# plp-cd_4-20.net
KiCad netlist of a schematic drawn in Altium Designer
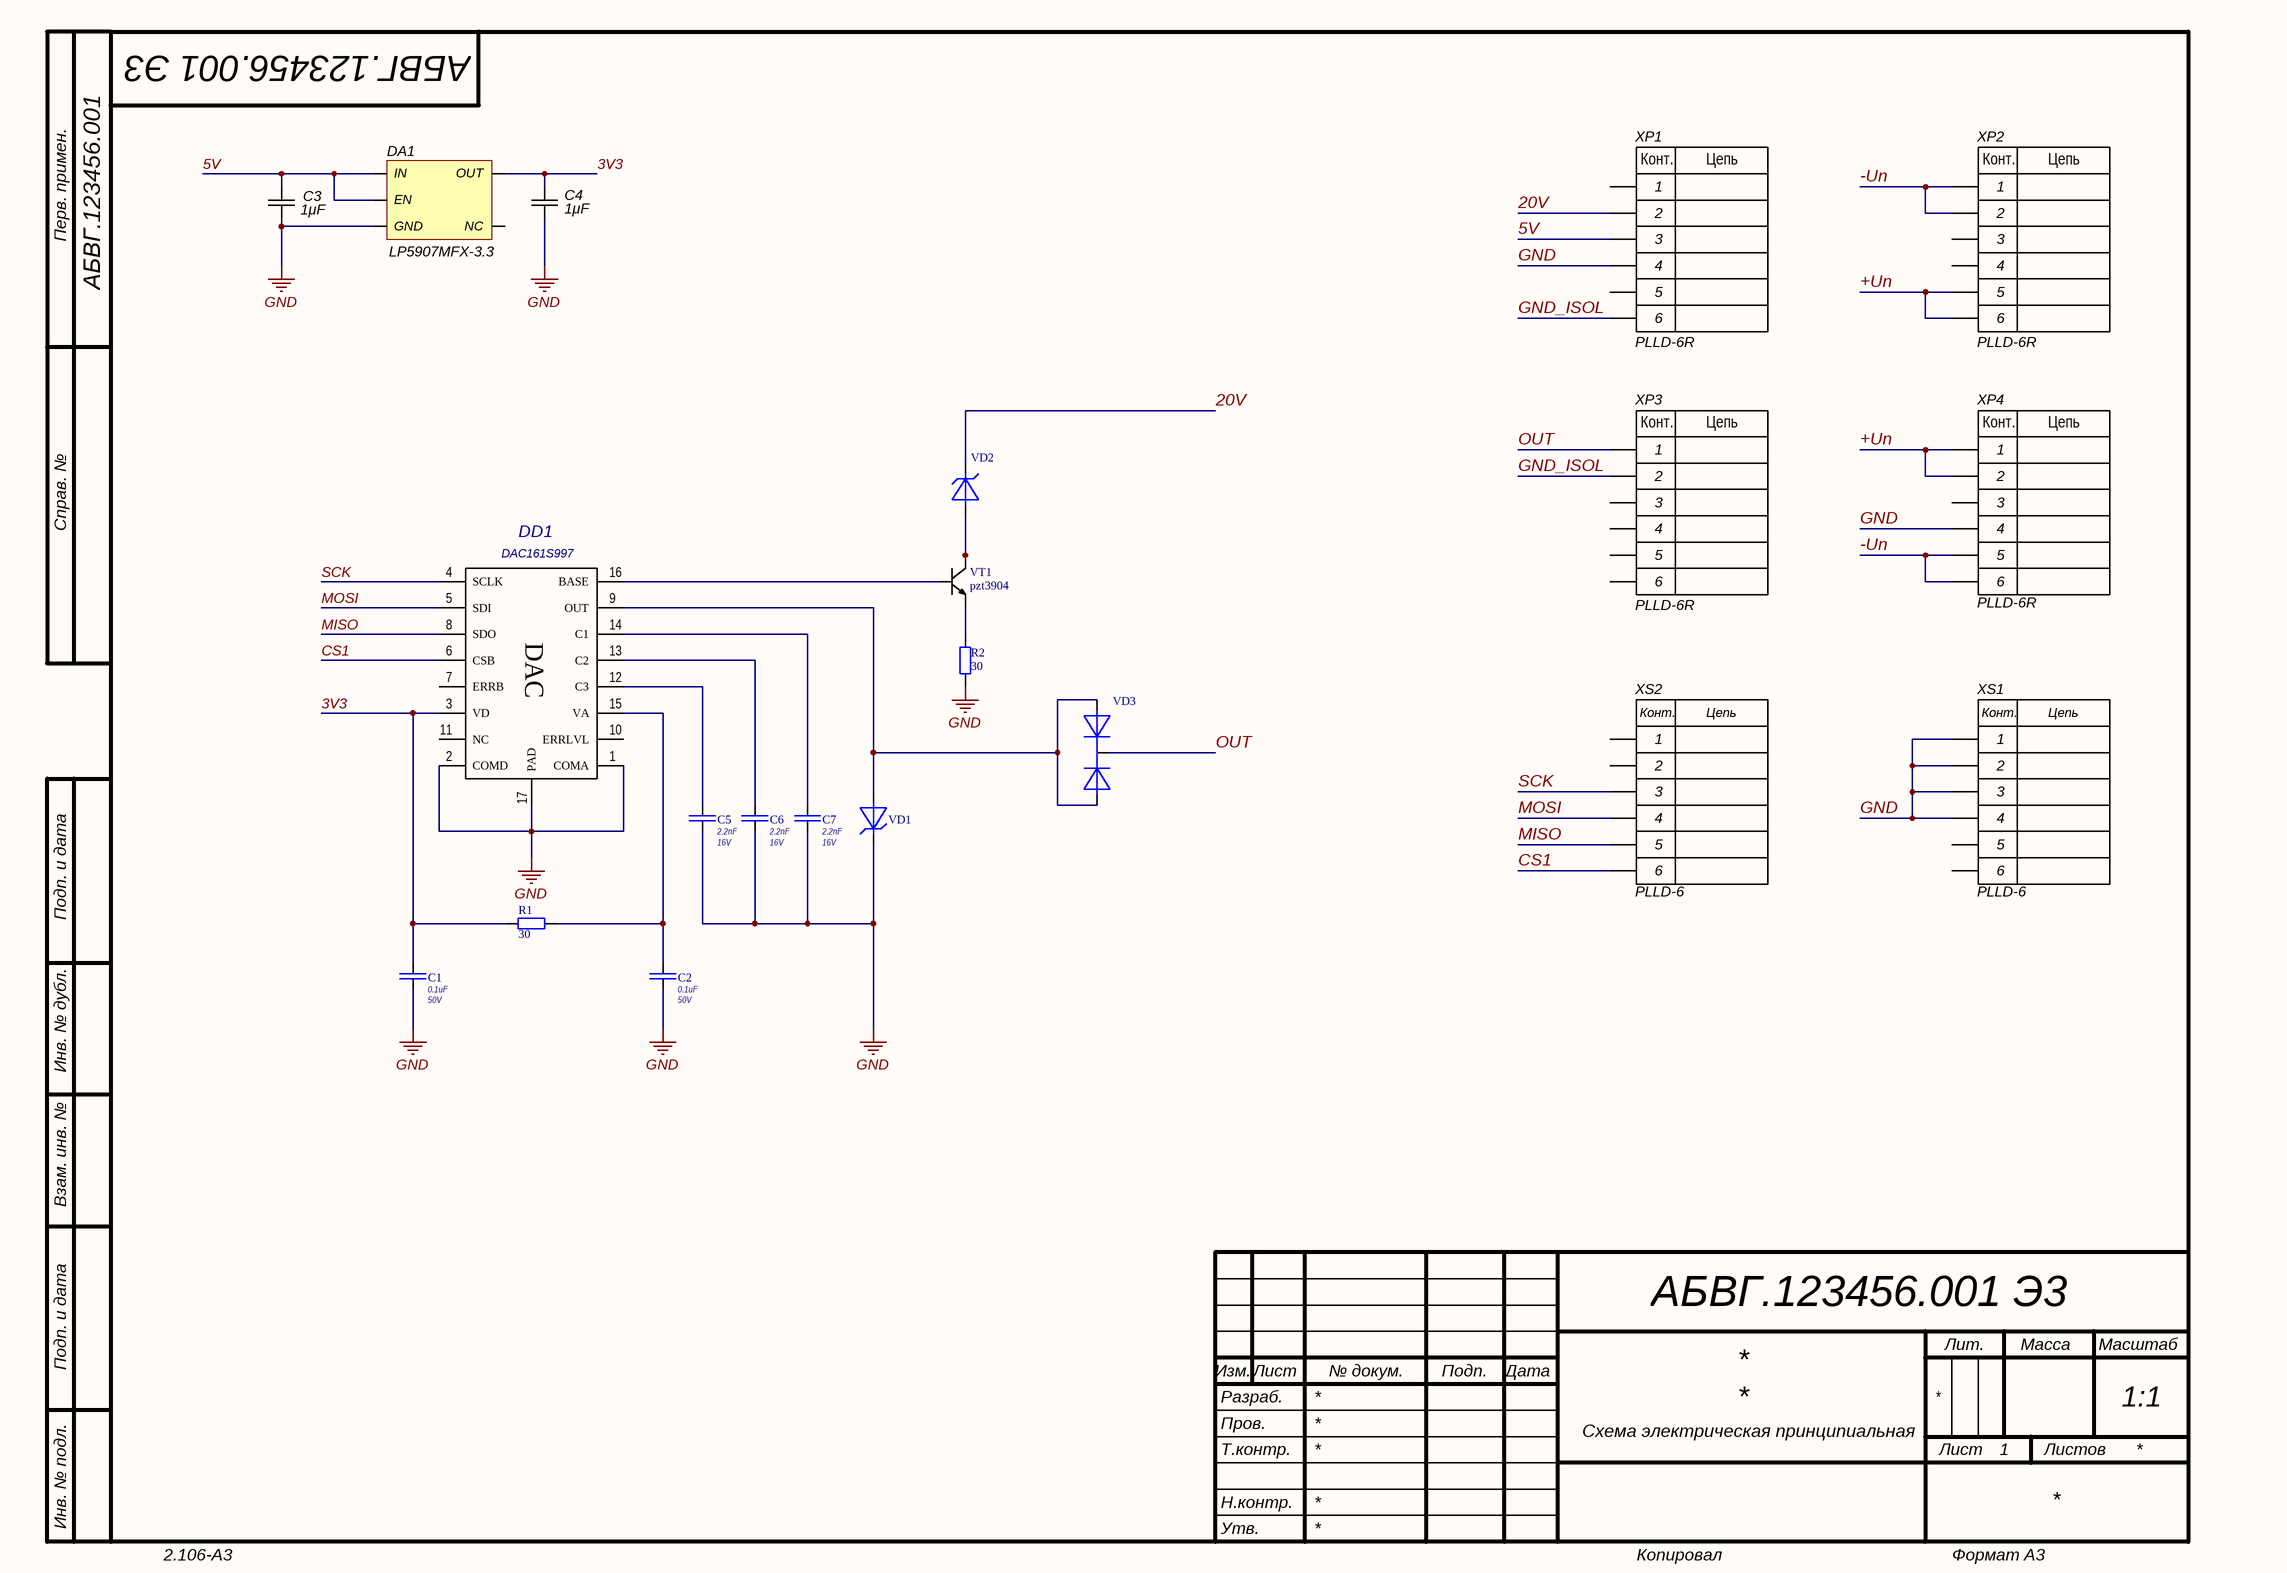
[diagram p0: plp-cd(4-20).SchDoc]

(export (version "E")
  (design (tool "Eeschema 10.0.6"))
  (components
    (comp (ref "C1")
      (value "0.1uF")
      (footprint "CAPC_0603(1608)X080L")
      (description "Конденсатор")
      (fields
        (field (name "MANUFACTURER") "Murata")
        (field (name "PARTNUMBER") "0603 - 0,1 мкФ ± 10 % - 50 В - X7R")
        (field (name "RATED DC VOLTAGE") "50V")
      )
      (libsource (lib "Chip Capacitor") (part "Capacitor Ceramic"))
    )
    (comp (ref "C2")
      (value "0.1uF")
      (footprint "CAPC_0603(1608)X080L")
      (description "Конденсатор")
      (fields
        (field (name "MANUFACTURER") "Murata")
        (field (name "PARTNUMBER") "0603 - 0,1 мкФ ± 10 % - 50 В - X7R")
        (field (name "RATED DC VOLTAGE") "50V")
      )
      (libsource (lib "Chip Capacitor") (part "Capacitor Ceramic"))
    )
    (comp (ref "C3")
      (value "1μF")
      (footprint "CAP: 0603")
      (fields
        (field (name "MANUFACTURER") "Yageo")
        (field (name "PARTNUMBER") "CC0603KRX7R7BB104")
        (field (name "VALUEMANUFACTURERPARTNUMBER") "Ceramic capacitor, 1μF, X7R, ±10%, 16V, 0603, -55...+125°C")
      )
      (libsource (lib "capacitor") (part "Ceramic_0603"))
    )
    (comp (ref "C4")
      (value "1μF")
      (footprint "CAP: 0603")
      (fields
        (field (name "MANUFACTURER") "Yageo")
        (field (name "PARTNUMBER") "CC0603KRX7R7BB104")
        (field (name "VALUEMANUFACTURERPARTNUMBER") "Ceramic capacitor, 1μF, X7R, ±10%, 16V, 0603, -55...+125°C")
      )
      (libsource (lib "capacitor") (part "Ceramic_0603"))
    )
    (comp (ref "C5")
      (value "2.2nF")
      (footprint "CAPC_0603(1608)X080L")
      (description "Конденсатор")
      (fields
        (field (name "MANUFACTURER") "Murata")
        (field (name "PARTNUMBER") "0603 - 0,1 мкФ ± 10 % - 50 В - X7R")
        (field (name "RATED DC VOLTAGE") "16V")
      )
      (libsource (lib "Chip Capacitor") (part "Capacitor Ceramic"))
    )
    (comp (ref "C6")
      (value "2.2nF")
      (footprint "CAPC_0603(1608)X080L")
      (description "Конденсатор")
      (fields
        (field (name "MANUFACTURER") "Murata")
        (field (name "PARTNUMBER") "0603 - 0,1 мкФ ± 10 % - 50 В - X7R")
        (field (name "RATED DC VOLTAGE") "16V")
      )
      (libsource (lib "Chip Capacitor") (part "Capacitor Ceramic"))
    )
    (comp (ref "C7")
      (value "2.2nF")
      (footprint "CAPC_0603(1608)X080L")
      (description "Конденсатор")
      (fields
        (field (name "MANUFACTURER") "Murata")
        (field (name "PARTNUMBER") "0603 - 0,1 мкФ ± 10 % - 50 В - X7R")
        (field (name "RATED DC VOLTAGE") "16V")
      )
      (libsource (lib "Chip Capacitor") (part "Capacitor Ceramic"))
    )
    (comp (ref "DA1")
      (value "LP5907MFX-3.3")
      (footprint "SOT23-5")
      (description "LDO 250 mA")
      (libsource (lib "ic-power-supply") (part "LP5907MFX-3.3"))
    )
    (comp (ref "DD1")
      (value "DAC161S997")
      (footprint "WQFN-16")
      (libsource (lib "TI DAC") (part "DAC161S997"))
    )
    (comp (ref "R1")
      (value "30")
      (footprint "RESC1608(0603)X04L")
      (description "Резистор")
      (fields (field (name "MANUFACTURER") "Bourns") (field (name "POWER") "1/10 Вт"))
      (libsource (lib "Chip Resistor") (part "R0603L"))
    )
    (comp (ref "R2")
      (value "30")
      (footprint "RESC1608(0603)X04L")
      (description "Резистор")
      (fields (field (name "MANUFACTURER") "Bourns") (field (name "POWER") "1/10 Вт"))
      (libsource (lib "") (part "R0603L_1"))
    )
    (comp (ref "VD1")
      (value "SM2T3V3A")
      (footprint "DO216-AA")
      (description "TVS Диод")
      (fields (field (name "MANUFACTURER") "ST Microelectronics"))
      (libsource (lib "ST Protection Diodes") (part "SM2T3V3A"))
    )
    (comp (ref "VD2")
      (value "SM2T")
      (footprint "DO216-AA")
      (description "TVS Диод")
      (fields (field (name "MANUFACTURER") "ST Microelectronics"))
      (libsource (lib "ST Protection Diodes") (part "SM2T"))
    )
    (comp (ref "VD3")
      (value "BAV70W")
      (footprint "SC-70")
      (description "Сборка диодная")
      (fields (field (name "MANUFACTURER") "NXP"))
      (libsource (lib "NXP Diodes") (part "BAV70W"))
    )
    (comp (ref "VT1")
      (value "pzt3904")
      (footprint "SOT223")
      (description "Транзистор")
      (fields (field (name "MANUFACTURER") "Fairchild Semiconductor"))
      (libsource (lib "Fairchild Transistor") (part "pzt3904"))
    )
    (comp (ref "XP1")
      (value "PLLD-6R")
      (footprint "CON: PLL-6(2x3R1.27male)")
      (description "Step 1.27 R")
      (libsource (lib "connector") (part "PLLD-6R(Male)"))
    )
    (comp (ref "XP2")
      (value "PLLD-6R")
      (footprint "CON: PLL-6(2x3R1.27male)")
      (description "Step 1.27 R")
      (libsource (lib "connector") (part "PLLD-6R(Male)"))
    )
    (comp (ref "XP3")
      (value "PLLD-6R")
      (footprint "CON: PLL-6(2x3R1.27male)")
      (description "Step 1.27 R")
      (libsource (lib "connector") (part "PLLD-6R(Male)"))
    )
    (comp (ref "XP4")
      (value "PLLD-6R")
      (footprint "CON: PLL-6(2x3R1.27male)")
      (description "Step 1.27 R")
      (libsource (lib "connector") (part "PLLD-6R(Male)"))
    )
    (comp (ref "XS1")
      (value "PLLD-6")
      (footprint "CON: PLL-6(2x3R1.27female)")
      (description "Step 1.27")
      (libsource (lib "connector") (part "PLLD-6(Female)"))
    )
    (comp (ref "XS2")
      (value "PLLD-6")
      (footprint "CON: PLL-6(2x3R1.27female)")
      (description "Step 1.27")
      (libsource (lib "connector") (part "PLLD-6(Female)"))
    )
  )
  (nets
    (net (code "1") (name "/+Uп") (class "Default")
      (node (ref "XP2") (pin "5") (pinfunction "5_5") (pintype "passive"))
      (node (ref "XP2") (pin "6") (pinfunction "6_6") (pintype "passive"))
      (node (ref "XP4") (pin "1") (pinfunction "1_1") (pintype "passive"))
      (node (ref "XP4") (pin "2") (pinfunction "2_2") (pintype "passive"))
    )
    (net (code "2") (name "/-Uп") (class "Default")
      (node (ref "XP2") (pin "1") (pinfunction "1_1") (pintype "passive"))
      (node (ref "XP2") (pin "2") (pinfunction "2_2") (pintype "passive"))
      (node (ref "XP4") (pin "5") (pinfunction "5_5") (pintype "passive"))
      (node (ref "XP4") (pin "6") (pinfunction "6_6") (pintype "passive"))
    )
    (net (code "3") (name "/3V3") (class "Default")
      (node (ref "C1") (pin "2") (pinfunction "2_2") (pintype "passive"))
      (node (ref "C4") (pin "2") (pinfunction "2_2") (pintype "passive"))
      (node (ref "DA1") (pin "5") (pinfunction "OUT_5") (pintype "passive"))
      (node (ref "DD1") (pin "3") (pinfunction "VD_3") (pintype "passive"))
      (node (ref "R1") (pin "1") (pinfunction "1_1") (pintype "passive"))
    )
    (net (code "4") (name "/5V") (class "Default")
      (node (ref "C3") (pin "2") (pinfunction "2_2") (pintype "passive"))
      (node (ref "DA1") (pin "1") (pinfunction "IN_1") (pintype "passive"))
      (node (ref "DA1") (pin "3") (pinfunction "EN_3") (pintype "passive"))
      (node (ref "XP1") (pin "3") (pinfunction "3_3") (pintype "passive"))
    )
    (net (code "5") (name "/20V") (class "Default")
      (node (ref "VD2") (pin "1") (pinfunction "C_1") (pintype "passive"))
      (node (ref "XP1") (pin "2") (pinfunction "2_2") (pintype "passive"))
    )
    (net (code "6") (name "/CS1") (class "Default")
      (node (ref "DD1") (pin "6") (pinfunction "CSB_6") (pintype "passive"))
      (node (ref "XS2") (pin "6") (pinfunction "6_6") (pintype "passive"))
    )
    (net (code "7") (name "/GND_ISOL") (class "Default")
      (node (ref "XP1") (pin "6") (pinfunction "6_6") (pintype "passive"))
      (node (ref "XP3") (pin "2") (pinfunction "2_2") (pintype "passive"))
    )
    (net (code "8") (name "/MISO") (class "Default")
      (node (ref "DD1") (pin "8") (pinfunction "SDO_8") (pintype "passive"))
      (node (ref "XS2") (pin "5") (pinfunction "5_5") (pintype "passive"))
    )
    (net (code "9") (name "/MOSI") (class "Default")
      (node (ref "DD1") (pin "5") (pinfunction "SDI_5") (pintype "passive"))
      (node (ref "XS2") (pin "4") (pinfunction "4_4") (pintype "passive"))
    )
    (net (code "10") (name "/OUT") (class "Default")
      (node (ref "VD3") (pin "3") (pinfunction "OC_3") (pintype "passive"))
      (node (ref "XP3") (pin "1") (pinfunction "1_1") (pintype "passive"))
    )
    (net (code "11") (name "/SCK") (class "Default")
      (node (ref "DD1") (pin "4") (pinfunction "SCLK_4") (pintype "passive"))
      (node (ref "XS2") (pin "3") (pinfunction "3_3") (pintype "passive"))
    )
    (net (code "12") (name "GND") (class "Default")
      (node (ref "C1") (pin "1") (pinfunction "1_1") (pintype "passive"))
      (node (ref "C2") (pin "1") (pinfunction "1_1") (pintype "passive"))
      (node (ref "C3") (pin "1") (pinfunction "1_1") (pintype "passive"))
      (node (ref "C4") (pin "1") (pinfunction "1_1") (pintype "passive"))
      (node (ref "C5") (pin "1") (pinfunction "1_1") (pintype "passive"))
      (node (ref "C6") (pin "1") (pinfunction "1_1") (pintype "passive"))
      (node (ref "C7") (pin "1") (pinfunction "1_1") (pintype "passive"))
      (node (ref "DA1") (pin "2") (pinfunction "GND_2") (pintype "passive"))
      (node (ref "DD1") (pin "1") (pinfunction "COMA_1") (pintype "passive"))
      (node (ref "DD1") (pin "17") (pinfunction "PAD_17") (pintype "passive"))
      (node (ref "DD1") (pin "2") (pinfunction "COMD_2") (pintype "passive"))
      (node (ref "R2") (pin "2") (pinfunction "2_2") (pintype "passive"))
      (node (ref "VD1") (pin "2") (pinfunction "C_2") (pintype "passive"))
      (node (ref "XP1") (pin "4") (pinfunction "4_4") (pintype "passive"))
      (node (ref "XP4") (pin "4") (pinfunction "4_4") (pintype "passive"))
      (node (ref "XS1") (pin "1") (pinfunction "1_1") (pintype "passive"))
      (node (ref "XS1") (pin "2") (pinfunction "2_2") (pintype "passive"))
      (node (ref "XS1") (pin "3") (pinfunction "3_3") (pintype "passive"))
      (node (ref "XS1") (pin "4") (pinfunction "4_4") (pintype "passive"))
    )
    (net (code "13") (name "Net-(DD1-BASE)") (class "Default")
      (node (ref "DD1") (pin "16") (pinfunction "BASE_16") (pintype "passive"))
      (node (ref "VT1") (pin "1") (pinfunction "Base_1") (pintype "passive"))
    )
    (net (code "14") (name "Net-(DD1-C1)") (class "Default")
      (node (ref "C7") (pin "2") (pinfunction "2_2") (pintype "passive"))
      (node (ref "DD1") (pin "14") (pinfunction "C1_14") (pintype "passive"))
    )
    (net (code "15") (name "Net-(DD1-C2)") (class "Default")
      (node (ref "C6") (pin "2") (pinfunction "2_2") (pintype "passive"))
      (node (ref "DD1") (pin "13") (pinfunction "C2_13") (pintype "passive"))
    )
    (net (code "16") (name "Net-(DD1-C3)") (class "Default")
      (node (ref "C5") (pin "2") (pinfunction "2_2") (pintype "passive"))
      (node (ref "DD1") (pin "12") (pinfunction "C3_12") (pintype "passive"))
    )
    (net (code "17") (name "Net-(DD1-OUT)") (class "Default")
      (node (ref "DD1") (pin "9") (pinfunction "OUT_9") (pintype "passive"))
      (node (ref "VD1") (pin "1") (pinfunction "A_1") (pintype "passive"))
      (node (ref "VD3") (pin "1") (pinfunction "A_1") (pintype "passive"))
      (node (ref "VD3") (pin "2") (pinfunction "A_2") (pintype "passive"))
    )
    (net (code "18") (name "Net-(DD1-VA)") (class "Default")
      (node (ref "C2") (pin "2") (pinfunction "2_2") (pintype "passive"))
      (node (ref "DD1") (pin "15") (pinfunction "VA_15") (pintype "passive"))
      (node (ref "R1") (pin "2") (pinfunction "2_2") (pintype "passive"))
    )
    (net (code "19") (name "Net-(VD2-A)") (class "Default")
      (node (ref "VD2") (pin "2") (pinfunction "A_2") (pintype "passive"))
      (node (ref "VT1") (pin "2") (pinfunction "Collector_2") (pintype "passive"))
      (node (ref "VT1") (pin "4") (pinfunction "Collector_4") (pintype "passive"))
    )
    (net (code "20") (name "Net-(VT1-Emitter)") (class "Default")
      (node (ref "R2") (pin "1") (pinfunction "1_1") (pintype "passive"))
      (node (ref "VT1") (pin "3") (pinfunction "Emitter_3") (pintype "passive"))
    )
    (net (code "21") (name "unconnected-(DA1-NC-Pad4)") (class "Default")
      (node (ref "DA1") (pin "4") (pinfunction "NC_4") (pintype "passive"))
    )
    (net (code "22") (name "unconnected-(DD1-ERRB-Pad7)") (class "Default")
      (node (ref "DD1") (pin "7") (pinfunction "ERRB_7") (pintype "passive"))
    )
    (net (code "23") (name "unconnected-(DD1-ERRLVL-Pad10)") (class "Default")
      (node (ref "DD1") (pin "10") (pinfunction "ERRLVL_10") (pintype "passive"))
    )
    (net (code "24") (name "unconnected-(DD1-NC-Pad11)") (class "Default")
      (node (ref "DD1") (pin "11") (pinfunction "NC_11") (pintype "passive"))
    )
    (net (code "25") (name "unconnected-(XP1-Pad1)") (class "Default")
      (node (ref "XP1") (pin "1") (pinfunction "1_1") (pintype "passive"))
    )
    (net (code "26") (name "unconnected-(XP1-Pad5)") (class "Default")
      (node (ref "XP1") (pin "5") (pinfunction "5_5") (pintype "passive"))
    )
    (net (code "27") (name "unconnected-(XP2-Pad3)") (class "Default")
      (node (ref "XP2") (pin "3") (pinfunction "3_3") (pintype "passive"))
    )
    (net (code "28") (name "unconnected-(XP2-Pad4)") (class "Default")
      (node (ref "XP2") (pin "4") (pinfunction "4_4") (pintype "passive"))
    )
    (net (code "29") (name "unconnected-(XP3-Pad3)") (class "Default")
      (node (ref "XP3") (pin "3") (pinfunction "3_3") (pintype "passive"))
    )
    (net (code "30") (name "unconnected-(XP3-Pad4)") (class "Default")
      (node (ref "XP3") (pin "4") (pinfunction "4_4") (pintype "passive"))
    )
    (net (code "31") (name "unconnected-(XP3-Pad5)") (class "Default")
      (node (ref "XP3") (pin "5") (pinfunction "5_5") (pintype "passive"))
    )
    (net (code "32") (name "unconnected-(XP3-Pad6)") (class "Default")
      (node (ref "XP3") (pin "6") (pinfunction "6_6") (pintype "passive"))
    )
    (net (code "33") (name "unconnected-(XP4-Pad3)") (class "Default")
      (node (ref "XP4") (pin "3") (pinfunction "3_3") (pintype "passive"))
    )
    (net (code "34") (name "unconnected-(XS1-Pad5)") (class "Default")
      (node (ref "XS1") (pin "5") (pinfunction "5_5") (pintype "passive"))
    )
    (net (code "35") (name "unconnected-(XS1-Pad6)") (class "Default")
      (node (ref "XS1") (pin "6") (pinfunction "6_6") (pintype "passive"))
    )
    (net (code "36") (name "unconnected-(XS2-Pad1)") (class "Default")
      (node (ref "XS2") (pin "1") (pinfunction "1_1") (pintype "passive"))
    )
    (net (code "37") (name "unconnected-(XS2-Pad2)") (class "Default")
      (node (ref "XS2") (pin "2") (pinfunction "2_2") (pintype "passive"))
    )
  )
)
